# node.net
KiCad netlist of a schematic drawn in EAGLE
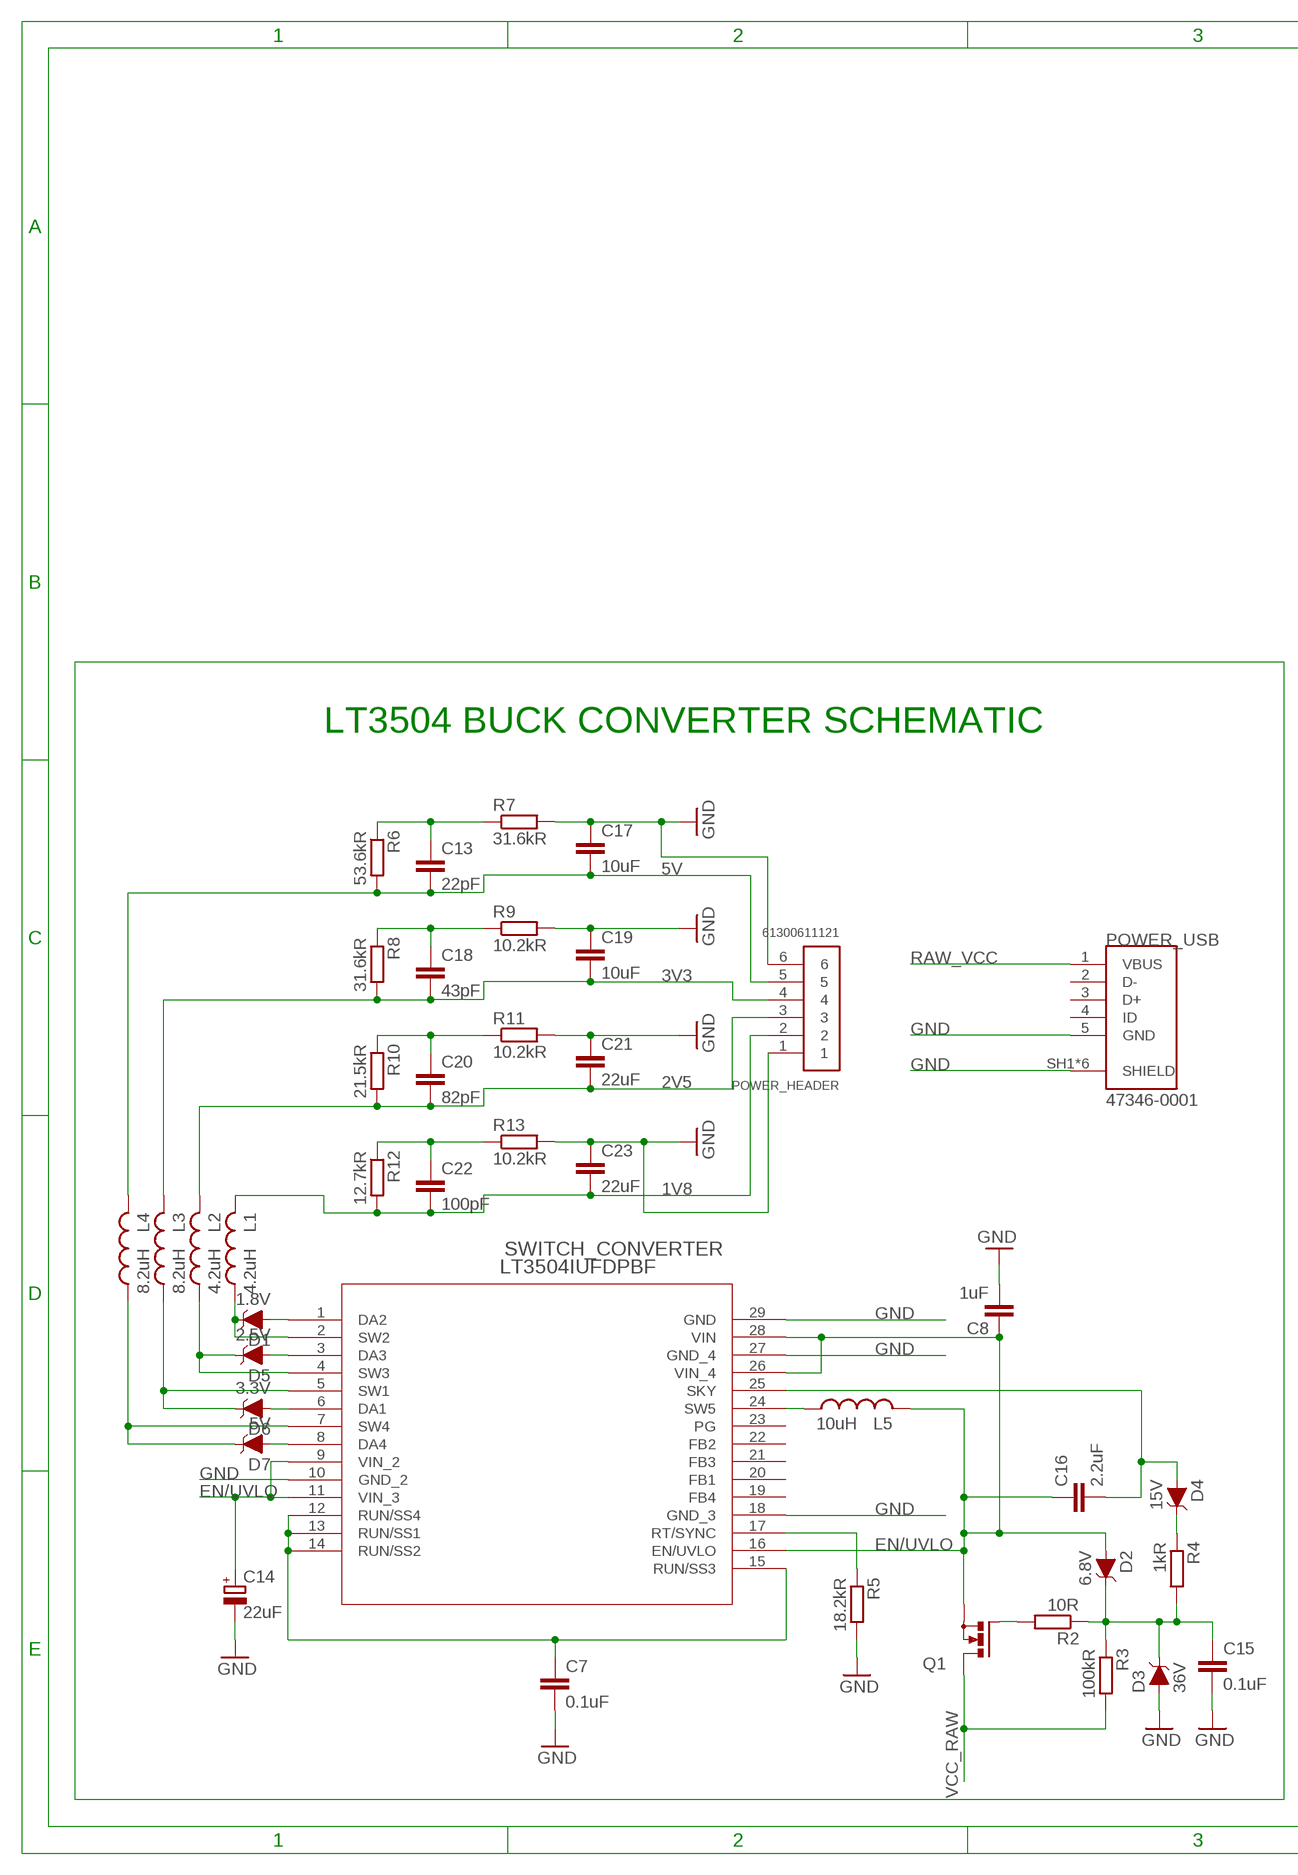
[diagram p0: schematic, sheet 1, part 1 of 2]
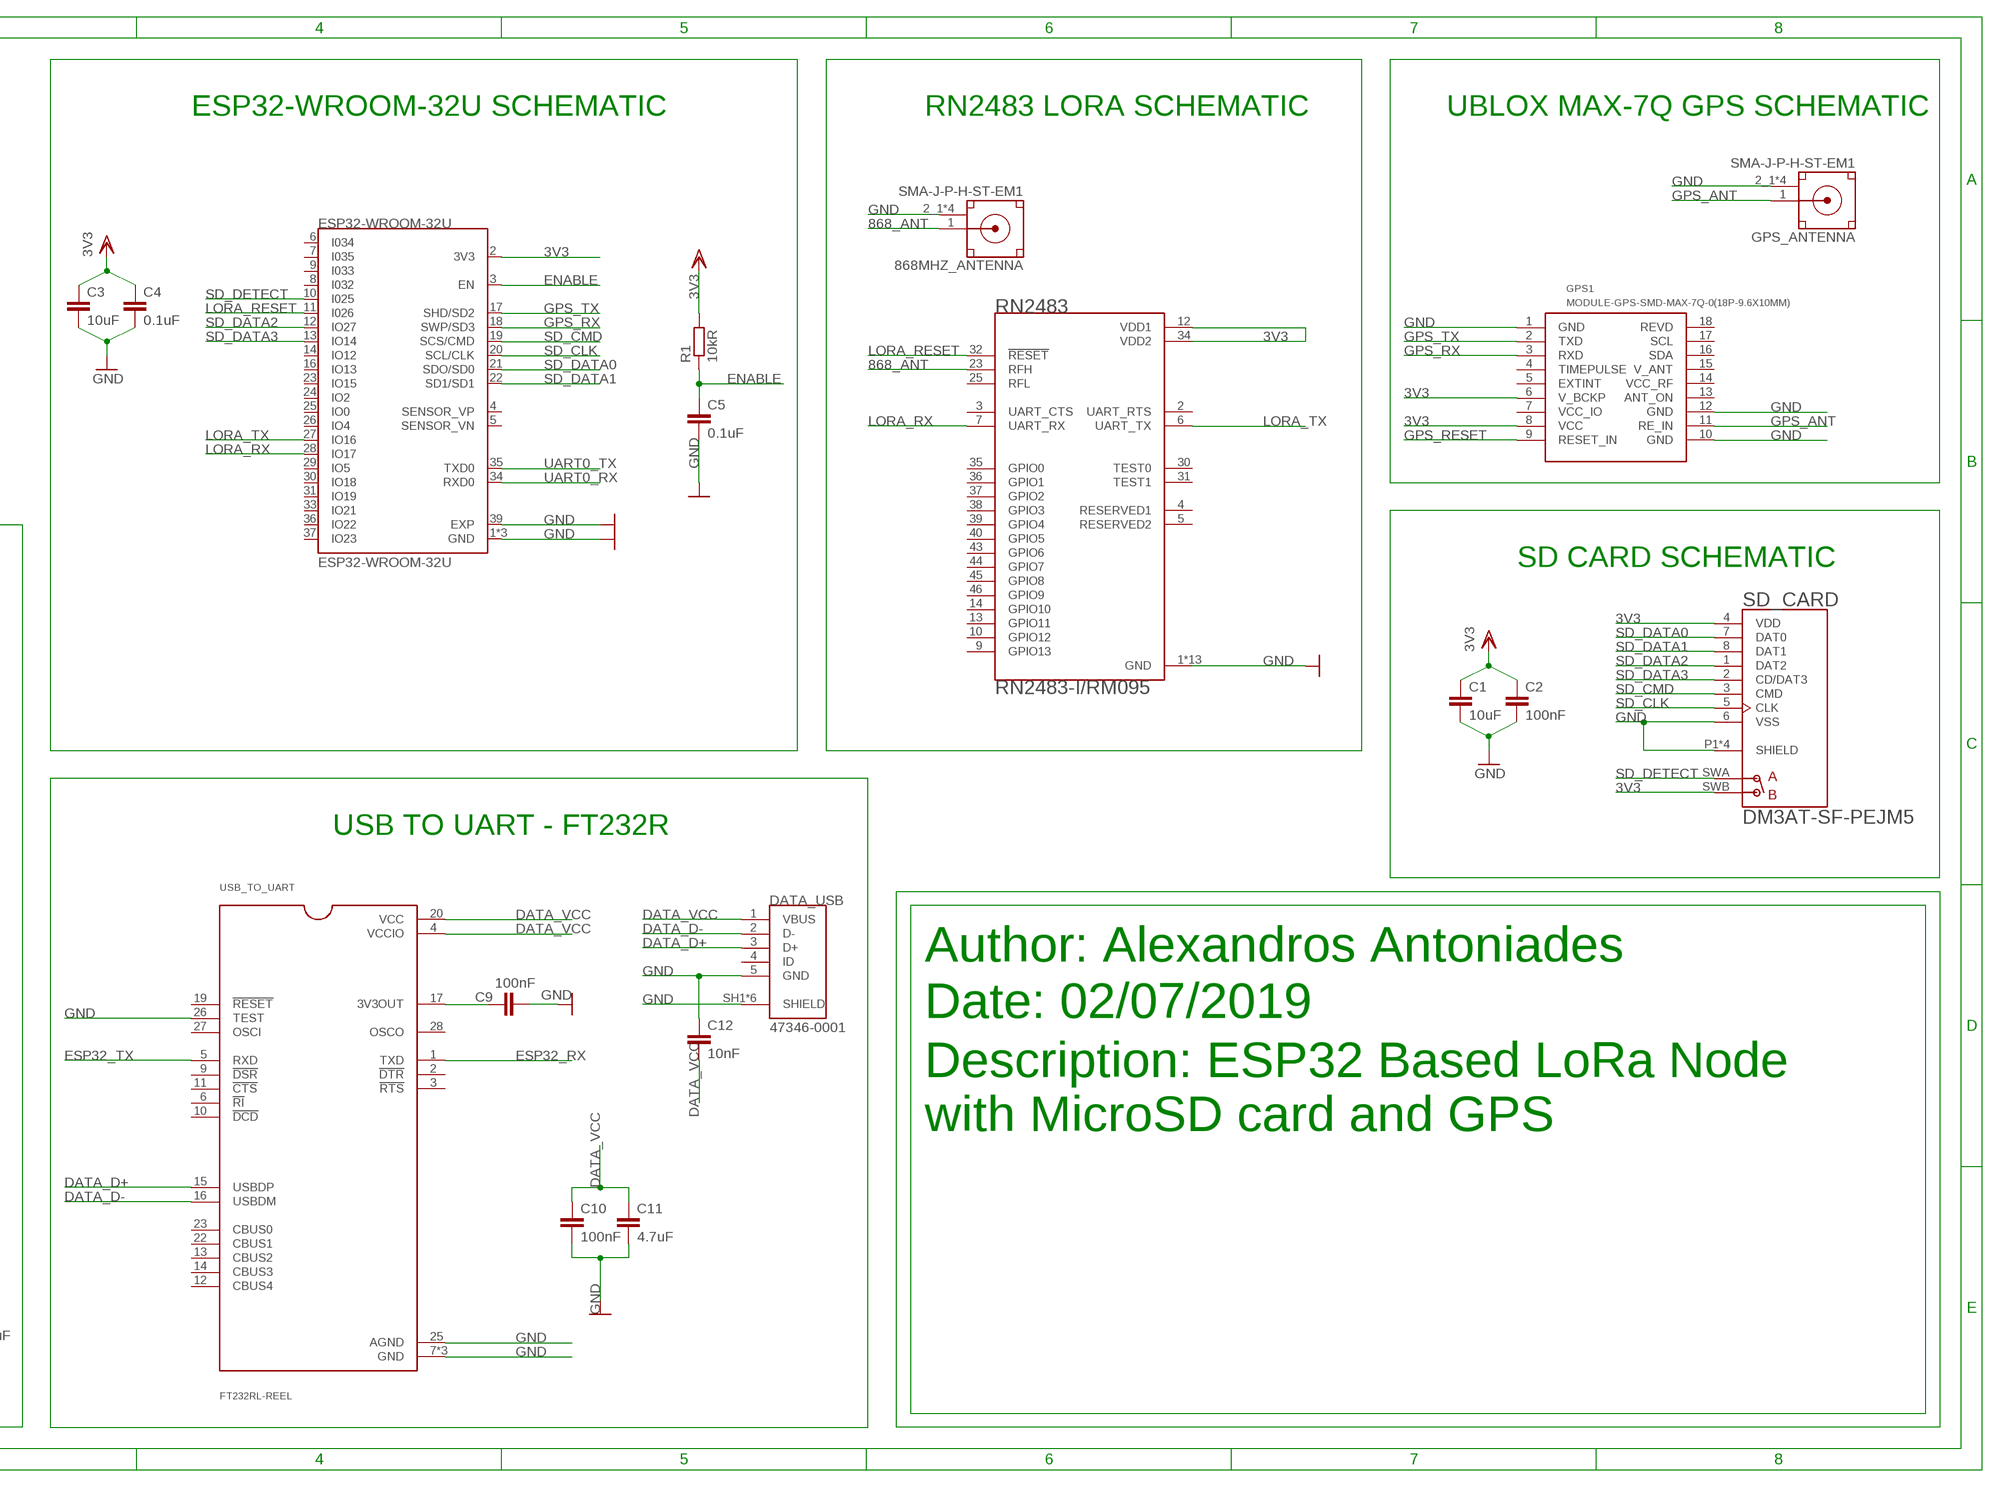
[diagram p1: schematic, sheet 1, part 2 of 2]

(export (version "E")
  (design (tool "Eeschema 10.0.6"))
  (components
    (comp (ref "868MHZ_ANTENNA")
      (value "SMA-J-P-H-ST-EM1")
      (footprint "eagle-import:SMA-J-P-H-ST-EM1")
      (fields (field (name "MF") "Samtec"))
      (libsource (lib "eagle-import") (part "SMA-J-P-H-ST-EM1"))
    )
    (comp (ref "C1")
      (value "10uF")
      (footprint "eagle-import:C0603")
      (libsource (lib "eagle-import") (part "C-EUC0603"))
    )
    (comp (ref "C2")
      (value "100nF")
      (footprint "eagle-import:C0603")
      (libsource (lib "eagle-import") (part "C-EUC0603"))
    )
    (comp (ref "C3")
      (value "10uF")
      (footprint "eagle-import:C0603")
      (libsource (lib "eagle-import") (part "C-EUC0603"))
    )
    (comp (ref "C4")
      (value "0.1uF")
      (footprint "eagle-import:C0603")
      (libsource (lib "eagle-import") (part "C-EUC0603"))
    )
    (comp (ref "C5")
      (value "0.1uF")
      (footprint "eagle-import:C0603")
      (libsource (lib "eagle-import") (part "C-EUC0603"))
    )
    (comp (ref "C7")
      (value "0.1uF")
      (footprint "eagle-import:C0603")
      (libsource (lib "eagle-import") (part "C-EUC0603"))
    )
    (comp (ref "C8")
      (value "1uF")
      (footprint "eagle-import:C0603")
      (libsource (lib "eagle-import") (part "C-EUC0603"))
    )
    (comp (ref "C9")
      (value "100nF")
      (footprint "eagle-import:C0603")
      (libsource (lib "eagle-import") (part "C-EUC0603"))
    )
    (comp (ref "C10")
      (value "100nF")
      (footprint "eagle-import:C0603")
      (libsource (lib "eagle-import") (part "C-EUC0603"))
    )
    (comp (ref "C11")
      (value "4.7uF")
      (footprint "eagle-import:C0603")
      (libsource (lib "eagle-import") (part "C-EUC0603"))
    )
    (comp (ref "C12")
      (value "10nF")
      (footprint "eagle-import:C0603")
      (libsource (lib "eagle-import") (part "C-EUC0603"))
    )
    (comp (ref "C13")
      (value "22pF")
      (footprint "eagle-import:C0603")
      (libsource (lib "eagle-import") (part "C-EUC0603"))
    )
    (comp (ref "C14")
      (value "22uF")
      (footprint "eagle-import:PANASONIC_C")
      (libsource (lib "eagle-import") (part "CPOL-EUC"))
    )
    (comp (ref "C15")
      (value "0.1uF")
      (footprint "eagle-import:C0603")
      (libsource (lib "eagle-import") (part "C-EUC0603"))
    )
    (comp (ref "C16")
      (value "2.2uF")
      (footprint "eagle-import:C0603")
      (libsource (lib "eagle-import") (part "C-EUC0603"))
    )
    (comp (ref "C17")
      (value "10uF")
      (footprint "eagle-import:C0603")
      (libsource (lib "eagle-import") (part "C-EUC0603"))
    )
    (comp (ref "C18")
      (value "43pF")
      (footprint "eagle-import:C0603")
      (libsource (lib "eagle-import") (part "C-EUC0603"))
    )
    (comp (ref "C19")
      (value "10uF")
      (footprint "eagle-import:C0603")
      (libsource (lib "eagle-import") (part "C-EUC0603"))
    )
    (comp (ref "C20")
      (value "82pF")
      (footprint "eagle-import:C0603")
      (libsource (lib "eagle-import") (part "C-EUC0603"))
    )
    (comp (ref "C21")
      (value "22uF")
      (footprint "eagle-import:C0603")
      (libsource (lib "eagle-import") (part "C-EUC0603"))
    )
    (comp (ref "C22")
      (value "100pF")
      (footprint "eagle-import:C0603")
      (libsource (lib "eagle-import") (part "C-EUC0603"))
    )
    (comp (ref "C23")
      (value "22uF")
      (footprint "eagle-import:C0603")
      (libsource (lib "eagle-import") (part "C-EUC0603"))
    )
    (comp (ref "D1")
      (value "1.8V")
      (footprint "eagle-import:PANASONIC_SMINI2-F5-B")
      (libsource (lib "eagle-import") (part "DIODE-ZENER-DZ2J150M0L"))
    )
    (comp (ref "D2")
      (value "6.8V")
      (footprint "eagle-import:PANASONIC_SMINI2-F5-B")
      (libsource (lib "eagle-import") (part "DIODE-ZENER-DZ2J150M0L"))
    )
    (comp (ref "D3")
      (value "36V")
      (footprint "eagle-import:PANASONIC_SMINI2-F5-B")
      (libsource (lib "eagle-import") (part "DIODE-ZENER-DZ2J150M0L"))
    )
    (comp (ref "D4")
      (value "15V")
      (footprint "eagle-import:PANASONIC_SMINI2-F5-B")
      (libsource (lib "eagle-import") (part "DIODE-ZENER-DZ2J150M0L"))
    )
    (comp (ref "D5")
      (value "2.5V")
      (footprint "eagle-import:PANASONIC_SMINI2-F5-B")
      (libsource (lib "eagle-import") (part "DIODE-ZENER-DZ2J150M0L"))
    )
    (comp (ref "D6")
      (value "3.3V")
      (footprint "eagle-import:PANASONIC_SMINI2-F5-B")
      (libsource (lib "eagle-import") (part "DIODE-ZENER-DZ2J150M0L"))
    )
    (comp (ref "D7")
      (value "5V")
      (footprint "eagle-import:PANASONIC_SMINI2-F5-B")
      (libsource (lib "eagle-import") (part "DIODE-ZENER-DZ2J150M0L"))
    )
    (comp (ref "DATA_USB")
      (value "47346-0001")
      (footprint "eagle-import:MOLEX_47346-0001")
      (fields (field (name "MF") "Molex"))
      (libsource (lib "eagle-import") (part "47346-0001"))
    )
    (comp (ref "ESP32-WROOM-32U")
      (value "ESP32-WROOM-32U")
      (footprint "eagle-import:XCVR_ESP32-WROOM-32U")
      (fields (field (name "MF") "Espressif Systems"))
      (libsource (lib "eagle-import") (part "ESP32-WROOM-32U"))
    )
    (comp (ref "GPS1")
      (value "MODULE-GPS-SMD-MAX-7Q-0(18P-9.6X10MM)")
      (footprint "eagle-import:GPS18P-SMD-1.1-10X9.6MM")
      (fields (field (name "MF") "u-blox") (field (name "MP") "MAX-7Q-0"))
      (libsource (lib "eagle-import") (part "MODULE-GPS-SMD-MAX-7Q-0(18P-9.6X10MM)"))
    )
    (comp (ref "GPS_ANTENNA")
      (value "SMA-J-P-H-ST-EM1")
      (footprint "eagle-import:SMA-J-P-H-ST-EM1")
      (fields (field (name "MF") "Samtec"))
      (libsource (lib "eagle-import") (part "SMA-J-P-H-ST-EM1"))
    )
    (comp (ref "L1")
      (value "4.2uH")
      (footprint "eagle-import:L4532P")
      (libsource (lib "eagle-import") (part "L-USL4532P"))
    )
    (comp (ref "L2")
      (value "4.2uH")
      (footprint "eagle-import:L4532P")
      (libsource (lib "eagle-import") (part "L-USL4532P"))
    )
    (comp (ref "L3")
      (value "8.2uH")
      (footprint "eagle-import:L4532P")
      (libsource (lib "eagle-import") (part "L-USL4532P"))
    )
    (comp (ref "L4")
      (value "8.2uH")
      (footprint "eagle-import:L4532P")
      (libsource (lib "eagle-import") (part "L-USL4532P"))
    )
    (comp (ref "L5")
      (value "10uH")
      (footprint "eagle-import:L4532P")
      (libsource (lib "eagle-import") (part "L-USL4532P"))
    )
    (comp (ref "POWER_HEADER")
      (value "61300611121")
      (footprint "eagle-import:61300611121")
      (fields
        (field (name "DIGI_KEY_PART_NUMBER") "732-5319-ND")
        (field (name "MANUFACTURER") "Wurth Electronics Inc.")
        (field (name "CREATED_BY") "PCBLayout.com")
      )
      (libsource (lib "eagle-import") (part "61300611121"))
    )
    (comp (ref "POWER_USB")
      (value "47346-0001")
      (footprint "eagle-import:MOLEX_47346-0001")
      (fields (field (name "MF") "Molex"))
      (libsource (lib "eagle-import") (part "47346-0001"))
    )
    (comp (ref "Q1")
      (value "N-MOSFET-SO8S")
      (footprint "eagle-import:SO-08")
      (libsource (lib "eagle-import") (part "N-MOSFET-SO8S"))
    )
    (comp (ref "R1")
      (value "10kR")
      (footprint "eagle-import:R0603")
      (libsource (lib "eagle-import") (part "R-EU_R0603"))
    )
    (comp (ref "R2")
      (value "10R")
      (footprint "eagle-import:R0603")
      (libsource (lib "eagle-import") (part "R-EU_R0603"))
    )
    (comp (ref "R3")
      (value "100kR")
      (footprint "eagle-import:R0603")
      (libsource (lib "eagle-import") (part "R-EU_R0603"))
    )
    (comp (ref "R4")
      (value "1kR")
      (footprint "eagle-import:R0603")
      (libsource (lib "eagle-import") (part "R-EU_R0603"))
    )
    (comp (ref "R5")
      (value "18.2kR")
      (footprint "eagle-import:R0603")
      (libsource (lib "eagle-import") (part "R-EU_R0603"))
    )
    (comp (ref "R6")
      (value "53.6kR")
      (footprint "eagle-import:R0603")
      (libsource (lib "eagle-import") (part "R-EU_R0603"))
    )
    (comp (ref "R7")
      (value "31.6kR")
      (footprint "eagle-import:R0603")
      (libsource (lib "eagle-import") (part "R-EU_R0603"))
    )
    (comp (ref "R8")
      (value "31.6kR")
      (footprint "eagle-import:R0603")
      (libsource (lib "eagle-import") (part "R-EU_R0603"))
    )
    (comp (ref "R9")
      (value "10.2kR")
      (footprint "eagle-import:R0603")
      (libsource (lib "eagle-import") (part "R-EU_R0603"))
    )
    (comp (ref "R10")
      (value "21.5kR")
      (footprint "eagle-import:R0603")
      (libsource (lib "eagle-import") (part "R-EU_R0603"))
    )
    (comp (ref "R11")
      (value "10.2kR")
      (footprint "eagle-import:R0603")
      (libsource (lib "eagle-import") (part "R-EU_R0603"))
    )
    (comp (ref "R12")
      (value "12.7kR")
      (footprint "eagle-import:R0603")
      (libsource (lib "eagle-import") (part "R-EU_R0603"))
    )
    (comp (ref "R13")
      (value "10.2kR")
      (footprint "eagle-import:R0603")
      (libsource (lib "eagle-import") (part "R-EU_R0603"))
    )
    (comp (ref "RN2483")
      (value "RN2483-I/RM095")
      (footprint "eagle-import:MICROCHIP_RN2483-I_RM095")
      (fields (field (name "MF") "Microchip"))
      (libsource (lib "eagle-import") (part "RN2483-I/RM095"))
    )
    (comp (ref "SD_CARD")
      (value "DM3AT-SF-PEJM5")
      (footprint "eagle-import:HRS_DM3AT-SF-PEJM5")
      (fields (field (name "MF") "Hirose"))
      (libsource (lib "eagle-import") (part "DM3AT-SF-PEJM5"))
    )
    (comp (ref "SWITCH_CONVERTER")
      (value "LT3504IUFDPBF")
      (footprint "eagle-import:QFN-28_UFD")
      (fields
        (field (name "DIGI-KEY_PART_NUMBER") "LT3504IUFD#PBF-ND")
        (field (name "MF") "Linear Technology")
        (field (name "MP") "LT3504IUFD#PBF")
      )
      (libsource (lib "eagle-import") (part "LT3504IUFDPBF"))
    )
    (comp (ref "USB_TO_UART")
      (value "FT232RL-REEL")
      (footprint "eagle-import:SOP65P780X200-28N")
      (fields (field (name "MF") "FTDI,"))
      (libsource (lib "eagle-import") (part "FT232RL-REEL"))
    )
  )
  (nets
    (net (code "1") (name "/1V8") (class "Default")
      (node (ref "C22") (pin "2") (pinfunction "2_2") (pintype "passive"))
      (node (ref "C23") (pin "2") (pinfunction "2_2") (pintype "passive"))
      (node (ref "L1") (pin "2") (pinfunction "2_2") (pintype "passive"))
      (node (ref "POWER_HEADER") (pin "2") (pinfunction "2_2") (pintype "passive"))
      (node (ref "R12") (pin "2") (pinfunction "2_2") (pintype "passive"))
    )
    (net (code "2") (name "/2V5") (class "Default")
      (node (ref "C20") (pin "2") (pinfunction "2_2") (pintype "passive"))
      (node (ref "C21") (pin "2") (pinfunction "2_2") (pintype "passive"))
      (node (ref "L2") (pin "2") (pinfunction "2_2") (pintype "passive"))
      (node (ref "POWER_HEADER") (pin "3") (pinfunction "3_3") (pintype "passive"))
      (node (ref "R10") (pin "2") (pinfunction "2_2") (pintype "passive"))
    )
    (net (code "3") (name "/5V") (class "Default")
      (node (ref "C13") (pin "2") (pinfunction "2_2") (pintype "passive"))
      (node (ref "C17") (pin "2") (pinfunction "2_2") (pintype "passive"))
      (node (ref "L4") (pin "2") (pinfunction "2_2") (pintype "passive"))
      (node (ref "POWER_HEADER") (pin "5") (pinfunction "5_5") (pintype "passive"))
      (node (ref "R6") (pin "2") (pinfunction "2_2") (pintype "passive"))
    )
    (net (code "4") (name "/868_ANT") (class "Default")
      (node (ref "868MHZ_ANTENNA") (pin "1") (pinfunction "SIGNAL_1") (pintype "passive"))
      (node (ref "RN2483") (pin "23") (pinfunction "RFH_23") (pintype "input"))
    )
    (net (code "5") (name "/DATA_D+") (class "Default")
      (node (ref "DATA_USB") (pin "3") (pinfunction "D+_3") (pintype "bidirectional"))
      (node (ref "USB_TO_UART") (pin "15") (pinfunction "USBDP_15") (pintype "bidirectional"))
    )
    (net (code "6") (name "/DATA_D-") (class "Default")
      (node (ref "DATA_USB") (pin "2") (pinfunction "D-_2") (pintype "bidirectional"))
      (node (ref "USB_TO_UART") (pin "16") (pinfunction "USBDM_16") (pintype "bidirectional"))
    )
    (net (code "7") (name "/DATA_VCC") (class "Default")
      (node (ref "C10") (pin "1") (pinfunction "1_1") (pintype "passive"))
      (node (ref "C11") (pin "1") (pinfunction "1_1") (pintype "passive"))
      (node (ref "C12") (pin "2") (pinfunction "2_2") (pintype "passive"))
      (node (ref "DATA_USB") (pin "1") (pinfunction "VBUS_1") (pintype "power_in"))
      (node (ref "USB_TO_UART") (pin "20") (pinfunction "VCC_20") (pintype "power_in"))
      (node (ref "USB_TO_UART") (pin "4") (pinfunction "VCCIO_4") (pintype "power_in"))
    )
    (net (code "8") (name "/ENABLE") (class "Default")
      (node (ref "C5") (pin "1") (pinfunction "1_1") (pintype "passive"))
      (node (ref "ESP32-WROOM-32U") (pin "3") (pinfunction "EN_3") (pintype "input"))
      (node (ref "R1") (pin "1") (pinfunction "1_1") (pintype "passive"))
    )
    (net (code "9") (name "/EN{slash}UVLO") (class "Default")
      (node (ref "C14") (pin "+") (pinfunction "+_+") (pintype "passive"))
      (node (ref "C16") (pin "1") (pinfunction "1_1") (pintype "passive"))
      (node (ref "C8") (pin "1") (pinfunction "1_1") (pintype "passive"))
      (node (ref "D2") (pin "A") (pinfunction "A_A") (pintype "passive"))
      (node (ref "L5") (pin "2") (pinfunction "2_2") (pintype "passive"))
      (node (ref "Q1") (pin "1") (pinfunction "S_1") (pintype "passive"))
      (node (ref "Q1") (pin "2") (pinfunction "S_2") (pintype "passive"))
      (node (ref "Q1") (pin "3") (pinfunction "S_3") (pintype "passive"))
      (node (ref "SWITCH_CONVERTER") (pin "11") (pinfunction "VIN_3_11") (pintype "input"))
      (node (ref "SWITCH_CONVERTER") (pin "16") (pinfunction "EN/UVLO_16") (pintype "bidirectional"))
      (node (ref "SWITCH_CONVERTER") (pin "26") (pinfunction "VIN_4_26") (pintype "input"))
      (node (ref "SWITCH_CONVERTER") (pin "28") (pinfunction "VIN_28") (pintype "input"))
      (node (ref "SWITCH_CONVERTER") (pin "9") (pinfunction "VIN_2_9") (pintype "input"))
    )
    (net (code "10") (name "/ESP32_RX") (class "Default")
      (node (ref "USB_TO_UART") (pin "1") (pinfunction "TXD_1") (pintype "output"))
    )
    (net (code "11") (name "/ESP32_TX") (class "Default")
      (node (ref "USB_TO_UART") (pin "5") (pinfunction "RXD_5") (pintype "input"))
    )
    (net (code "12") (name "/GPS_ANT") (class "Default")
      (node (ref "GPS1") (pin "11") (pinfunction "RE_IN_11") (pintype "bidirectional"))
      (node (ref "GPS_ANTENNA") (pin "1") (pinfunction "SIGNAL_1") (pintype "passive"))
    )
    (net (code "13") (name "/GPS_RESET") (class "Default")
      (node (ref "GPS1") (pin "9") (pinfunction "RESET_IN_9") (pintype "bidirectional"))
    )
    (net (code "14") (name "/GPS_RX") (class "Default")
      (node (ref "ESP32-WROOM-32U") (pin "18") (pinfunction "SWP/SD3_18") (pintype "bidirectional"))
      (node (ref "GPS1") (pin "3") (pinfunction "RXD_3") (pintype "bidirectional"))
    )
    (net (code "15") (name "/GPS_TX") (class "Default")
      (node (ref "ESP32-WROOM-32U") (pin "17") (pinfunction "SHD/SD2_17") (pintype "bidirectional"))
      (node (ref "GPS1") (pin "2") (pinfunction "TXD_2") (pintype "bidirectional"))
    )
    (net (code "16") (name "/LORA_RESET") (class "Default")
      (node (ref "ESP32-WROOM-32U") (pin "11") (pinfunction "I026_11") (pintype "bidirectional"))
      (node (ref "RN2483") (pin "32") (pinfunction "~{RESET}_32") (pintype "input"))
    )
    (net (code "17") (name "/LORA_RX") (class "Default")
      (node (ref "ESP32-WROOM-32U") (pin "28") (pinfunction "IO17_28") (pintype "bidirectional"))
      (node (ref "RN2483") (pin "7") (pinfunction "UART_RX_7") (pintype "input"))
    )
    (net (code "18") (name "/LORA_TX") (class "Default")
      (node (ref "ESP32-WROOM-32U") (pin "27") (pinfunction "IO16_27") (pintype "bidirectional"))
      (node (ref "RN2483") (pin "6") (pinfunction "UART_TX_6") (pintype "output"))
    )
    (net (code "19") (name "/RAW_VCC") (class "Default")
      (node (ref "POWER_USB") (pin "1") (pinfunction "VBUS_1") (pintype "power_in"))
    )
    (net (code "20") (name "/SD_CLK") (class "Default")
      (node (ref "ESP32-WROOM-32U") (pin "20") (pinfunction "SCL/CLK_20") (pintype "bidirectional"))
      (node (ref "SD_CARD") (pin "5") (pinfunction "CLK_5") (pintype "bidirectional"))
    )
    (net (code "21") (name "/SD_CMD") (class "Default")
      (node (ref "ESP32-WROOM-32U") (pin "19") (pinfunction "SCS/CMD_19") (pintype "bidirectional"))
      (node (ref "SD_CARD") (pin "3") (pinfunction "CMD_3") (pintype "bidirectional"))
    )
    (net (code "22") (name "/SD_DATA0") (class "Default")
      (node (ref "ESP32-WROOM-32U") (pin "21") (pinfunction "SDO/SD0_21") (pintype "bidirectional"))
      (node (ref "SD_CARD") (pin "7") (pinfunction "DAT0_7") (pintype "bidirectional"))
    )
    (net (code "23") (name "/SD_DATA1") (class "Default")
      (node (ref "ESP32-WROOM-32U") (pin "22") (pinfunction "SD1/SD1_22") (pintype "bidirectional"))
      (node (ref "SD_CARD") (pin "8") (pinfunction "DAT1_8") (pintype "bidirectional"))
    )
    (net (code "24") (name "/SD_DATA2") (class "Default")
      (node (ref "ESP32-WROOM-32U") (pin "12") (pinfunction "IO27_12") (pintype "bidirectional"))
      (node (ref "SD_CARD") (pin "1") (pinfunction "DAT2_1") (pintype "bidirectional"))
    )
    (net (code "25") (name "/SD_DATA3") (class "Default")
      (node (ref "ESP32-WROOM-32U") (pin "13") (pinfunction "IO14_13") (pintype "bidirectional"))
      (node (ref "SD_CARD") (pin "2") (pinfunction "CD/DAT3_2") (pintype "bidirectional"))
    )
    (net (code "26") (name "/SD_DETECT") (class "Default")
      (node (ref "ESP32-WROOM-32U") (pin "10") (pinfunction "I025_10") (pintype "bidirectional"))
      (node (ref "SD_CARD") (pin "SWA") (pinfunction "A_SWA") (pintype "bidirectional"))
    )
    (net (code "27") (name "/UART0_RX") (class "Default")
      (node (ref "ESP32-WROOM-32U") (pin "34") (pinfunction "RXD0_34") (pintype "bidirectional"))
    )
    (net (code "28") (name "/UART0_TX") (class "Default")
      (node (ref "ESP32-WROOM-32U") (pin "35") (pinfunction "TXD0_35") (pintype "bidirectional"))
    )
    (net (code "29") (name "/VCC_RAW") (class "Default")
      (node (ref "Q1") (pin "5") (pinfunction "D_5") (pintype "passive"))
      (node (ref "Q1") (pin "6") (pinfunction "D_6") (pintype "passive"))
      (node (ref "Q1") (pin "7") (pinfunction "D_7") (pintype "passive"))
      (node (ref "Q1") (pin "8") (pinfunction "D_8") (pintype "passive"))
      (node (ref "R3") (pin "2") (pinfunction "2_2") (pintype "passive"))
    )
    (net (code "30") (name "GND") (class "Default")
      (node (ref "868MHZ_ANTENNA") (pin "2_1") (pinfunction "GND_2_1") (pintype "power_in"))
      (node (ref "868MHZ_ANTENNA") (pin "2_2") (pinfunction "GND_2_2") (pintype "power_in"))
      (node (ref "868MHZ_ANTENNA") (pin "3_1") (pinfunction "GND_3_1") (pintype "power_in"))
      (node (ref "868MHZ_ANTENNA") (pin "3_2") (pinfunction "GND_3_2") (pintype "power_in"))
      (node (ref "C1") (pin "2") (pinfunction "2_2") (pintype "passive"))
      (node (ref "C10") (pin "2") (pinfunction "2_2") (pintype "passive"))
      (node (ref "C11") (pin "2") (pinfunction "2_2") (pintype "passive"))
      (node (ref "C12") (pin "1") (pinfunction "1_1") (pintype "passive"))
      (node (ref "C14") (pin "-") (pinfunction "-_-") (pintype "passive"))
      (node (ref "C15") (pin "2") (pinfunction "2_2") (pintype "passive"))
      (node (ref "C17") (pin "1") (pinfunction "1_1") (pintype "passive"))
      (node (ref "C19") (pin "1") (pinfunction "1_1") (pintype "passive"))
      (node (ref "C2") (pin "2") (pinfunction "2_2") (pintype "passive"))
      (node (ref "C21") (pin "1") (pinfunction "1_1") (pintype "passive"))
      (node (ref "C23") (pin "1") (pinfunction "1_1") (pintype "passive"))
      (node (ref "C3") (pin "2") (pinfunction "2_2") (pintype "passive"))
      (node (ref "C4") (pin "2") (pinfunction "2_2") (pintype "passive"))
      (node (ref "C5") (pin "2") (pinfunction "2_2") (pintype "passive"))
      (node (ref "C7") (pin "2") (pinfunction "2_2") (pintype "passive"))
      (node (ref "C8") (pin "2") (pinfunction "2_2") (pintype "passive"))
      (node (ref "C9") (pin "2") (pinfunction "2_2") (pintype "passive"))
      (node (ref "D3") (pin "A") (pinfunction "A_A") (pintype "passive"))
      (node (ref "DATA_USB") (pin "5") (pinfunction "GND_5") (pintype "power_in"))
      (node (ref "DATA_USB") (pin "SH1") (pinfunction "SHIELD_SH1") (pintype "passive"))
      (node (ref "DATA_USB") (pin "SH2") (pinfunction "SHIELD_SH2") (pintype "passive"))
      (node (ref "DATA_USB") (pin "SH3") (pinfunction "SHIELD_SH3") (pintype "passive"))
      (node (ref "DATA_USB") (pin "SH4") (pinfunction "SHIELD_SH4") (pintype "passive"))
      (node (ref "DATA_USB") (pin "SH5") (pinfunction "SHIELD_SH5") (pintype "passive"))
      (node (ref "DATA_USB") (pin "SH6") (pinfunction "SHIELD_SH6") (pintype "passive"))
      (node (ref "ESP32-WROOM-32U") (pin "1") (pinfunction "GND_1") (pintype "power_in"))
      (node (ref "ESP32-WROOM-32U") (pin "15") (pinfunction "GND_15") (pintype "power_in"))
      (node (ref "ESP32-WROOM-32U") (pin "38") (pinfunction "GND_38") (pintype "power_in"))
      (node (ref "ESP32-WROOM-32U") (pin "39") (pinfunction "EXP_39") (pintype "power_in"))
      (node (ref "GPS1") (pin "1") (pinfunction "GND_1") (pintype "bidirectional"))
      (node (ref "GPS1") (pin "10") (pinfunction "GND_10") (pintype "bidirectional"))
      (node (ref "GPS1") (pin "12") (pinfunction "GND_12") (pintype "bidirectional"))
      (node (ref "GPS_ANTENNA") (pin "2_1") (pinfunction "GND_2_1") (pintype "power_in"))
      (node (ref "GPS_ANTENNA") (pin "2_2") (pinfunction "GND_2_2") (pintype "power_in"))
      (node (ref "GPS_ANTENNA") (pin "3_1") (pinfunction "GND_3_1") (pintype "power_in"))
      (node (ref "GPS_ANTENNA") (pin "3_2") (pinfunction "GND_3_2") (pintype "power_in"))
      (node (ref "POWER_HEADER") (pin "1") (pinfunction "1_1") (pintype "passive"))
      (node (ref "POWER_HEADER") (pin "6") (pinfunction "6_6") (pintype "passive"))
      (node (ref "POWER_USB") (pin "5") (pinfunction "GND_5") (pintype "power_in"))
      (node (ref "POWER_USB") (pin "SH1") (pinfunction "SHIELD_SH1") (pintype "passive"))
      (node (ref "POWER_USB") (pin "SH2") (pinfunction "SHIELD_SH2") (pintype "passive"))
      (node (ref "POWER_USB") (pin "SH3") (pinfunction "SHIELD_SH3") (pintype "passive"))
      (node (ref "POWER_USB") (pin "SH4") (pinfunction "SHIELD_SH4") (pintype "passive"))
      (node (ref "POWER_USB") (pin "SH5") (pinfunction "SHIELD_SH5") (pintype "passive"))
      (node (ref "POWER_USB") (pin "SH6") (pinfunction "SHIELD_SH6") (pintype "passive"))
      (node (ref "R11") (pin "2") (pinfunction "2_2") (pintype "passive"))
      (node (ref "R13") (pin "2") (pinfunction "2_2") (pintype "passive"))
      (node (ref "R5") (pin "2") (pinfunction "2_2") (pintype "passive"))
      (node (ref "R7") (pin "2") (pinfunction "2_2") (pintype "passive"))
      (node (ref "R9") (pin "2") (pinfunction "2_2") (pintype "passive"))
      (node (ref "RN2483") (pin "1") (pinfunction "GND_1") (pintype "passive"))
      (node (ref "RN2483") (pin "11") (pinfunction "GND_11") (pintype "passive"))
      (node (ref "RN2483") (pin "20") (pinfunction "GND_20") (pintype "passive"))
      (node (ref "RN2483") (pin "21") (pinfunction "GND_21") (pintype "passive"))
      (node (ref "RN2483") (pin "22") (pinfunction "GND_22") (pintype "passive"))
      (node (ref "RN2483") (pin "24") (pinfunction "GND_24") (pintype "passive"))
      (node (ref "RN2483") (pin "26") (pinfunction "GND_26") (pintype "passive"))
      (node (ref "RN2483") (pin "27") (pinfunction "GND_27") (pintype "passive"))
      (node (ref "RN2483") (pin "28") (pinfunction "GND_28") (pintype "passive"))
      (node (ref "RN2483") (pin "33") (pinfunction "GND_33") (pintype "passive"))
      (node (ref "RN2483") (pin "41") (pinfunction "GND_41") (pintype "passive"))
      (node (ref "RN2483") (pin "47") (pinfunction "GND_47") (pintype "passive"))
      (node (ref "RN2483") (pin "8") (pinfunction "GND_8") (pintype "passive"))
      (node (ref "SD_CARD") (pin "6") (pinfunction "VSS_6") (pintype "power_in"))
      (node (ref "SD_CARD") (pin "P1") (pinfunction "SHIELD_P1") (pintype "passive"))
      (node (ref "SD_CARD") (pin "P2") (pinfunction "SHIELD_P2") (pintype "passive"))
      (node (ref "SD_CARD") (pin "P3") (pinfunction "SHIELD_P3") (pintype "passive"))
      (node (ref "SD_CARD") (pin "P4") (pinfunction "SHIELD_P4") (pintype "passive"))
      (node (ref "SWITCH_CONVERTER") (pin "10") (pinfunction "GND_2_10") (pintype "power_in"))
      (node (ref "SWITCH_CONVERTER") (pin "18") (pinfunction "GND_3_18") (pintype "power_in"))
      (node (ref "SWITCH_CONVERTER") (pin "27") (pinfunction "GND_4_27") (pintype "power_in"))
      (node (ref "SWITCH_CONVERTER") (pin "29") (pinfunction "GND_29") (pintype "power_in"))
      (node (ref "USB_TO_UART") (pin "18") (pinfunction "GND_18") (pintype "passive"))
      (node (ref "USB_TO_UART") (pin "21") (pinfunction "GND_21") (pintype "passive"))
      (node (ref "USB_TO_UART") (pin "25") (pinfunction "AGND_25") (pintype "passive"))
      (node (ref "USB_TO_UART") (pin "26") (pinfunction "TEST_26") (pintype "input"))
      (node (ref "USB_TO_UART") (pin "7") (pinfunction "GND_7") (pintype "passive"))
    )
    (net (code "31") (name "Net-(C13-Pad1)") (class "Default")
      (node (ref "C13") (pin "1") (pinfunction "1_1") (pintype "passive"))
      (node (ref "R6") (pin "1") (pinfunction "1_1") (pintype "passive"))
      (node (ref "R7") (pin "1") (pinfunction "1_1") (pintype "passive"))
    )
    (net (code "32") (name "Net-(C15-Pad1)") (class "Default")
      (node (ref "C15") (pin "1") (pinfunction "1_1") (pintype "passive"))
      (node (ref "D2") (pin "C") (pinfunction "C_C") (pintype "passive"))
      (node (ref "D3") (pin "C") (pinfunction "C_C") (pintype "passive"))
      (node (ref "R2") (pin "1") (pinfunction "1_1") (pintype "passive"))
      (node (ref "R3") (pin "1") (pinfunction "1_1") (pintype "passive"))
      (node (ref "R4") (pin "2") (pinfunction "2_2") (pintype "passive"))
    )
    (net (code "33") (name "Net-(C18-Pad1)") (class "Default")
      (node (ref "C18") (pin "1") (pinfunction "1_1") (pintype "passive"))
      (node (ref "R8") (pin "1") (pinfunction "1_1") (pintype "passive"))
      (node (ref "R9") (pin "1") (pinfunction "1_1") (pintype "passive"))
    )
    (net (code "34") (name "Net-(C20-Pad1)") (class "Default")
      (node (ref "C20") (pin "1") (pinfunction "1_1") (pintype "passive"))
      (node (ref "R10") (pin "1") (pinfunction "1_1") (pintype "passive"))
      (node (ref "R11") (pin "1") (pinfunction "1_1") (pintype "passive"))
    )
    (net (code "35") (name "Net-(C22-Pad1)") (class "Default")
      (node (ref "C22") (pin "1") (pinfunction "1_1") (pintype "passive"))
      (node (ref "R12") (pin "1") (pinfunction "1_1") (pintype "passive"))
      (node (ref "R13") (pin "1") (pinfunction "1_1") (pintype "passive"))
    )
    (net (code "36") (name "Net-(D4-PadC)") (class "Default")
      (node (ref "D4") (pin "C") (pinfunction "C_C") (pintype "passive"))
      (node (ref "R4") (pin "1") (pinfunction "1_1") (pintype "passive"))
    )
    (net (code "37") (name "Net-(Q1-G)") (class "Default")
      (node (ref "Q1") (pin "4") (pinfunction "G_4") (pintype "passive"))
      (node (ref "R2") (pin "2") (pinfunction "2_2") (pintype "passive"))
    )
    (net (code "38") (name "Net-(SWITCH_CONVERTER-DA1)") (class "Default")
      (node (ref "D6") (pin "A") (pinfunction "A_A") (pintype "passive"))
      (node (ref "SWITCH_CONVERTER") (pin "6") (pinfunction "DA1_6") (pintype "passive"))
    )
    (net (code "39") (name "Net-(SWITCH_CONVERTER-DA2)") (class "Default")
      (node (ref "D1") (pin "A") (pinfunction "A_A") (pintype "passive"))
      (node (ref "SWITCH_CONVERTER") (pin "1") (pinfunction "DA2_1") (pintype "passive"))
    )
    (net (code "40") (name "Net-(SWITCH_CONVERTER-DA3)") (class "Default")
      (node (ref "D5") (pin "A") (pinfunction "A_A") (pintype "passive"))
      (node (ref "SWITCH_CONVERTER") (pin "3") (pinfunction "DA3_3") (pintype "passive"))
    )
    (net (code "41") (name "Net-(SWITCH_CONVERTER-DA4)") (class "Default")
      (node (ref "D7") (pin "A") (pinfunction "A_A") (pintype "passive"))
      (node (ref "SWITCH_CONVERTER") (pin "8") (pinfunction "DA4_8") (pintype "passive"))
    )
    (net (code "42") (name "Net-(SWITCH_CONVERTER-RT{slash}SYNC)") (class "Default")
      (node (ref "R5") (pin "1") (pinfunction "1_1") (pintype "passive"))
      (node (ref "SWITCH_CONVERTER") (pin "17") (pinfunction "RT/SYNC_17") (pintype "bidirectional"))
    )
    (net (code "43") (name "Net-(SWITCH_CONVERTER-RUN{slash}SS1)") (class "Default")
      (node (ref "C7") (pin "1") (pinfunction "1_1") (pintype "passive"))
      (node (ref "SWITCH_CONVERTER") (pin "12") (pinfunction "RUN/SS4_12") (pintype "output"))
      (node (ref "SWITCH_CONVERTER") (pin "13") (pinfunction "RUN/SS1_13") (pintype "output"))
      (node (ref "SWITCH_CONVERTER") (pin "14") (pinfunction "RUN/SS2_14") (pintype "output"))
      (node (ref "SWITCH_CONVERTER") (pin "15") (pinfunction "RUN/SS3_15") (pintype "output"))
    )
    (net (code "44") (name "Net-(SWITCH_CONVERTER-SKY)") (class "Default")
      (node (ref "C16") (pin "2") (pinfunction "2_2") (pintype "passive"))
      (node (ref "D4") (pin "A") (pinfunction "A_A") (pintype "passive"))
      (node (ref "SWITCH_CONVERTER") (pin "25") (pinfunction "SKY_25") (pintype "output"))
    )
    (net (code "45") (name "Net-(SWITCH_CONVERTER-SW1)") (class "Default")
      (node (ref "D6") (pin "C") (pinfunction "C_C") (pintype "passive"))
      (node (ref "L3") (pin "1") (pinfunction "1_1") (pintype "passive"))
      (node (ref "SWITCH_CONVERTER") (pin "5") (pinfunction "SW1_5") (pintype "output"))
    )
    (net (code "46") (name "Net-(SWITCH_CONVERTER-SW2)") (class "Default")
      (node (ref "D1") (pin "C") (pinfunction "C_C") (pintype "passive"))
      (node (ref "L1") (pin "1") (pinfunction "1_1") (pintype "passive"))
      (node (ref "SWITCH_CONVERTER") (pin "2") (pinfunction "SW2_2") (pintype "output"))
    )
    (net (code "47") (name "Net-(SWITCH_CONVERTER-SW3)") (class "Default")
      (node (ref "D5") (pin "C") (pinfunction "C_C") (pintype "passive"))
      (node (ref "L2") (pin "1") (pinfunction "1_1") (pintype "passive"))
      (node (ref "SWITCH_CONVERTER") (pin "4") (pinfunction "SW3_4") (pintype "output"))
    )
    (net (code "48") (name "Net-(SWITCH_CONVERTER-SW4)") (class "Default")
      (node (ref "D7") (pin "C") (pinfunction "C_C") (pintype "passive"))
      (node (ref "L4") (pin "1") (pinfunction "1_1") (pintype "passive"))
      (node (ref "SWITCH_CONVERTER") (pin "7") (pinfunction "SW4_7") (pintype "output"))
    )
    (net (code "49") (name "Net-(SWITCH_CONVERTER-SW5)") (class "Default")
      (node (ref "L5") (pin "1") (pinfunction "1_1") (pintype "passive"))
      (node (ref "SWITCH_CONVERTER") (pin "24") (pinfunction "SW5_24") (pintype "passive"))
    )
    (net (code "50") (name "Net-(USB_TO_UART-3V3OUT)") (class "Default")
      (node (ref "C9") (pin "1") (pinfunction "1_1") (pintype "passive"))
      (node (ref "USB_TO_UART") (pin "17") (pinfunction "3V3OUT_17") (pintype "output"))
    )
    (net (code "51") (name "VDD") (class "Default")
      (node (ref "C1") (pin "1") (pinfunction "1_1") (pintype "passive"))
      (node (ref "C18") (pin "2") (pinfunction "2_2") (pintype "passive"))
      (node (ref "C19") (pin "2") (pinfunction "2_2") (pintype "passive"))
      (node (ref "C2") (pin "1") (pinfunction "1_1") (pintype "passive"))
      (node (ref "C3") (pin "1") (pinfunction "1_1") (pintype "passive"))
      (node (ref "C4") (pin "1") (pinfunction "1_1") (pintype "passive"))
      (node (ref "ESP32-WROOM-32U") (pin "2") (pinfunction "3V3_2") (pintype "power_in"))
      (node (ref "GPS1") (pin "6") (pinfunction "V_BCKP_6") (pintype "bidirectional"))
      (node (ref "GPS1") (pin "8") (pinfunction "VCC_8") (pintype "bidirectional"))
      (node (ref "L3") (pin "2") (pinfunction "2_2") (pintype "passive"))
      (node (ref "POWER_HEADER") (pin "4") (pinfunction "4_4") (pintype "passive"))
      (node (ref "R1") (pin "2") (pinfunction "2_2") (pintype "passive"))
      (node (ref "R8") (pin "2") (pinfunction "2_2") (pintype "passive"))
      (node (ref "RN2483") (pin "12") (pinfunction "VDD1_12") (pintype "power_in"))
      (node (ref "RN2483") (pin "34") (pinfunction "VDD2_34") (pintype "power_in"))
      (node (ref "SD_CARD") (pin "4") (pinfunction "VDD_4") (pintype "power_in"))
      (node (ref "SD_CARD") (pin "SWB") (pinfunction "B_SWB") (pintype "bidirectional"))
    )
    (net (code "52") (name "unconnected-(DATA_USB-ID-Pad4)") (class "Default")
      (node (ref "DATA_USB") (pin "4") (pinfunction "ID_4") (pintype "passive"))
    )
    (net (code "53") (name "unconnected-(ESP32-WROOM-32U-I032-Pad8)") (class "Default")
      (node (ref "ESP32-WROOM-32U") (pin "8") (pinfunction "I032_8") (pintype "bidirectional"))
    )
    (net (code "54") (name "unconnected-(ESP32-WROOM-32U-I033-Pad9)") (class "Default")
      (node (ref "ESP32-WROOM-32U") (pin "9") (pinfunction "I033_9") (pintype "bidirectional"))
    )
    (net (code "55") (name "unconnected-(ESP32-WROOM-32U-I034-Pad6)") (class "Default")
      (node (ref "ESP32-WROOM-32U") (pin "6") (pinfunction "I034_6") (pintype "input"))
    )
    (net (code "56") (name "unconnected-(ESP32-WROOM-32U-I035-Pad7)") (class "Default")
      (node (ref "ESP32-WROOM-32U") (pin "7") (pinfunction "I035_7") (pintype "input"))
    )
    (net (code "57") (name "unconnected-(ESP32-WROOM-32U-IO0-Pad25)") (class "Default")
      (node (ref "ESP32-WROOM-32U") (pin "25") (pinfunction "IO0_25") (pintype "bidirectional"))
    )
    (net (code "58") (name "unconnected-(ESP32-WROOM-32U-IO2-Pad24)") (class "Default")
      (node (ref "ESP32-WROOM-32U") (pin "24") (pinfunction "IO2_24") (pintype "bidirectional"))
    )
    (net (code "59") (name "unconnected-(ESP32-WROOM-32U-IO4-Pad26)") (class "Default")
      (node (ref "ESP32-WROOM-32U") (pin "26") (pinfunction "IO4_26") (pintype "bidirectional"))
    )
    (net (code "60") (name "unconnected-(ESP32-WROOM-32U-IO5-Pad29)") (class "Default")
      (node (ref "ESP32-WROOM-32U") (pin "29") (pinfunction "IO5_29") (pintype "bidirectional"))
    )
    (net (code "61") (name "unconnected-(ESP32-WROOM-32U-IO12-Pad14)") (class "Default")
      (node (ref "ESP32-WROOM-32U") (pin "14") (pinfunction "IO12_14") (pintype "bidirectional"))
    )
    (net (code "62") (name "unconnected-(ESP32-WROOM-32U-IO13-Pad16)") (class "Default")
      (node (ref "ESP32-WROOM-32U") (pin "16") (pinfunction "IO13_16") (pintype "bidirectional"))
    )
    (net (code "63") (name "unconnected-(ESP32-WROOM-32U-IO15-Pad23)") (class "Default")
      (node (ref "ESP32-WROOM-32U") (pin "23") (pinfunction "IO15_23") (pintype "bidirectional"))
    )
    (net (code "64") (name "unconnected-(ESP32-WROOM-32U-IO18-Pad30)") (class "Default")
      (node (ref "ESP32-WROOM-32U") (pin "30") (pinfunction "IO18_30") (pintype "bidirectional"))
    )
    (net (code "65") (name "unconnected-(ESP32-WROOM-32U-IO19-Pad31)") (class "Default")
      (node (ref "ESP32-WROOM-32U") (pin "31") (pinfunction "IO19_31") (pintype "bidirectional"))
    )
    (net (code "66") (name "unconnected-(ESP32-WROOM-32U-IO21-Pad33)") (class "Default")
      (node (ref "ESP32-WROOM-32U") (pin "33") (pinfunction "IO21_33") (pintype "bidirectional"))
    )
    (net (code "67") (name "unconnected-(ESP32-WROOM-32U-IO22-Pad36)") (class "Default")
      (node (ref "ESP32-WROOM-32U") (pin "36") (pinfunction "IO22_36") (pintype "bidirectional"))
    )
    (net (code "68") (name "unconnected-(ESP32-WROOM-32U-IO23-Pad37)") (class "Default")
      (node (ref "ESP32-WROOM-32U") (pin "37") (pinfunction "IO23_37") (pintype "bidirectional"))
    )
    (net (code "69") (name "unconnected-(ESP32-WROOM-32U-SENSOR_VN-Pad5)") (class "Default")
      (node (ref "ESP32-WROOM-32U") (pin "5") (pinfunction "SENSOR_VN_5") (pintype "input"))
    )
    (net (code "70") (name "unconnected-(ESP32-WROOM-32U-SENSOR_VP-Pad4)") (class "Default")
      (node (ref "ESP32-WROOM-32U") (pin "4") (pinfunction "SENSOR_VP_4") (pintype "input"))
    )
    (net (code "71") (name "unconnected-(GPS1-ANT_ON-Pad13)") (class "Default")
      (node (ref "GPS1") (pin "13") (pinfunction "ANT_ON_13") (pintype "bidirectional"))
    )
    (net (code "72") (name "unconnected-(GPS1-EXTINT-Pad5)") (class "Default")
      (node (ref "GPS1") (pin "5") (pinfunction "EXTINT_5") (pintype "bidirectional"))
    )
    (net (code "73") (name "unconnected-(GPS1-REVD-Pad18)") (class "Default")
      (node (ref "GPS1") (pin "18") (pinfunction "REVD_18") (pintype "bidirectional"))
    )
    (net (code "74") (name "unconnected-(GPS1-SCL-Pad17)") (class "Default")
      (node (ref "GPS1") (pin "17") (pinfunction "SCL_17") (pintype "bidirectional"))
    )
    (net (code "75") (name "unconnected-(GPS1-SDA-Pad16)") (class "Default")
      (node (ref "GPS1") (pin "16") (pinfunction "SDA_16") (pintype "bidirectional"))
    )
    (net (code "76") (name "unconnected-(GPS1-TIMEPULSE-Pad4)") (class "Default")
      (node (ref "GPS1") (pin "4") (pinfunction "TIMEPULSE_4") (pintype "bidirectional"))
    )
    (net (code "77") (name "unconnected-(GPS1-VCC_IO-Pad7)") (class "Default")
      (node (ref "GPS1") (pin "7") (pinfunction "VCC_IO_7") (pintype "bidirectional"))
    )
    (net (code "78") (name "unconnected-(GPS1-VCC_RF-Pad14)") (class "Default")
      (node (ref "GPS1") (pin "14") (pinfunction "VCC_RF_14") (pintype "bidirectional"))
    )
    (net (code "79") (name "unconnected-(GPS1-V_ANT-Pad15)") (class "Default")
      (node (ref "GPS1") (pin "15") (pinfunction "V_ANT_15") (pintype "bidirectional"))
    )
    (net (code "80") (name "unconnected-(POWER_USB-D+-Pad3)") (class "Default")
      (node (ref "POWER_USB") (pin "3") (pinfunction "D+_3") (pintype "bidirectional"))
    )
    (net (code "81") (name "unconnected-(POWER_USB-D--Pad2)") (class "Default")
      (node (ref "POWER_USB") (pin "2") (pinfunction "D-_2") (pintype "bidirectional"))
    )
    (net (code "82") (name "unconnected-(POWER_USB-ID-Pad4)") (class "Default")
      (node (ref "POWER_USB") (pin "4") (pinfunction "ID_4") (pintype "passive"))
    )
    (net (code "83") (name "unconnected-(RN2483-GPIO0-Pad35)") (class "Default")
      (node (ref "RN2483") (pin "35") (pinfunction "GPIO0_35") (pintype "bidirectional"))
    )
    (net (code "84") (name "unconnected-(RN2483-GPIO1-Pad36)") (class "Default")
      (node (ref "RN2483") (pin "36") (pinfunction "GPIO1_36") (pintype "bidirectional"))
    )
    (net (code "85") (name "unconnected-(RN2483-GPIO2-Pad37)") (class "Default")
      (node (ref "RN2483") (pin "37") (pinfunction "GPIO2_37") (pintype "bidirectional"))
    )
    (net (code "86") (name "unconnected-(RN2483-GPIO3-Pad38)") (class "Default")
      (node (ref "RN2483") (pin "38") (pinfunction "GPIO3_38") (pintype "bidirectional"))
    )
    (net (code "87") (name "unconnected-(RN2483-GPIO4-Pad39)") (class "Default")
      (node (ref "RN2483") (pin "39") (pinfunction "GPIO4_39") (pintype "bidirectional"))
    )
    (net (code "88") (name "unconnected-(RN2483-GPIO5-Pad40)") (class "Default")
      (node (ref "RN2483") (pin "40") (pinfunction "GPIO5_40") (pintype "bidirectional"))
    )
    (net (code "89") (name "unconnected-(RN2483-GPIO6-Pad43)") (class "Default")
      (node (ref "RN2483") (pin "43") (pinfunction "GPIO6_43") (pintype "bidirectional"))
    )
    (net (code "90") (name "unconnected-(RN2483-GPIO7-Pad44)") (class "Default")
      (node (ref "RN2483") (pin "44") (pinfunction "GPIO7_44") (pintype "bidirectional"))
    )
    (net (code "91") (name "unconnected-(RN2483-GPIO8-Pad45)") (class "Default")
      (node (ref "RN2483") (pin "45") (pinfunction "GPIO8_45") (pintype "bidirectional"))
    )
    (net (code "92") (name "unconnected-(RN2483-GPIO9-Pad46)") (class "Default")
      (node (ref "RN2483") (pin "46") (pinfunction "GPIO9_46") (pintype "bidirectional"))
    )
    (net (code "93") (name "unconnected-(RN2483-GPIO10-Pad14)") (class "Default")
      (node (ref "RN2483") (pin "14") (pinfunction "GPIO10_14") (pintype "bidirectional"))
    )
    (net (code "94") (name "unconnected-(RN2483-GPIO11-Pad13)") (class "Default")
      (node (ref "RN2483") (pin "13") (pinfunction "GPIO11_13") (pintype "bidirectional"))
    )
    (net (code "95") (name "unconnected-(RN2483-GPIO12-Pad10)") (class "Default")
      (node (ref "RN2483") (pin "10") (pinfunction "GPIO12_10") (pintype "bidirectional"))
    )
    (net (code "96") (name "unconnected-(RN2483-GPIO13-Pad9)") (class "Default")
      (node (ref "RN2483") (pin "9") (pinfunction "GPIO13_9") (pintype "bidirectional"))
    )
    (net (code "97") (name "unconnected-(RN2483-RESERVED1-Pad4)") (class "Default")
      (node (ref "RN2483") (pin "4") (pinfunction "RESERVED1_4") (pintype "passive"))
    )
    (net (code "98") (name "unconnected-(RN2483-RESERVED2-Pad5)") (class "Default")
      (node (ref "RN2483") (pin "5") (pinfunction "RESERVED2_5") (pintype "passive"))
    )
    (net (code "99") (name "unconnected-(RN2483-RFL-Pad25)") (class "Default")
      (node (ref "RN2483") (pin "25") (pinfunction "RFL_25") (pintype "input"))
    )
    (net (code "100") (name "unconnected-(RN2483-TEST0-Pad30)") (class "Default")
      (node (ref "RN2483") (pin "30") (pinfunction "TEST0_30") (pintype "passive"))
    )
    (net (code "101") (name "unconnected-(RN2483-TEST1-Pad31)") (class "Default")
      (node (ref "RN2483") (pin "31") (pinfunction "TEST1_31") (pintype "passive"))
    )
    (net (code "102") (name "unconnected-(RN2483-UART_CTS-Pad3)") (class "Default")
      (node (ref "RN2483") (pin "3") (pinfunction "UART_CTS_3") (pintype "input"))
    )
    (net (code "103") (name "unconnected-(RN2483-UART_RTS-Pad2)") (class "Default")
      (node (ref "RN2483") (pin "2") (pinfunction "UART_RTS_2") (pintype "output"))
    )
    (net (code "104") (name "unconnected-(SWITCH_CONVERTER-FB1-Pad20)") (class "Default")
      (node (ref "SWITCH_CONVERTER") (pin "20") (pinfunction "FB1_20") (pintype "output"))
    )
    (net (code "105") (name "unconnected-(SWITCH_CONVERTER-FB2-Pad22)") (class "Default")
      (node (ref "SWITCH_CONVERTER") (pin "22") (pinfunction "FB2_22") (pintype "output"))
    )
    (net (code "106") (name "unconnected-(SWITCH_CONVERTER-FB3-Pad21)") (class "Default")
      (node (ref "SWITCH_CONVERTER") (pin "21") (pinfunction "FB3_21") (pintype "output"))
    )
    (net (code "107") (name "unconnected-(SWITCH_CONVERTER-FB4-Pad19)") (class "Default")
      (node (ref "SWITCH_CONVERTER") (pin "19") (pinfunction "FB4_19") (pintype "output"))
    )
    (net (code "108") (name "unconnected-(SWITCH_CONVERTER-PG-Pad23)") (class "Default")
      (node (ref "SWITCH_CONVERTER") (pin "23") (pinfunction "PG_23") (pintype "output"))
    )
    (net (code "109") (name "unconnected-(USB_TO_UART-CBUS0-Pad23)") (class "Default")
      (node (ref "USB_TO_UART") (pin "23") (pinfunction "CBUS0_23") (pintype "bidirectional"))
    )
    (net (code "110") (name "unconnected-(USB_TO_UART-CBUS1-Pad22)") (class "Default")
      (node (ref "USB_TO_UART") (pin "22") (pinfunction "CBUS1_22") (pintype "bidirectional"))
    )
    (net (code "111") (name "unconnected-(USB_TO_UART-CBUS2-Pad13)") (class "Default")
      (node (ref "USB_TO_UART") (pin "13") (pinfunction "CBUS2_13") (pintype "bidirectional"))
    )
    (net (code "112") (name "unconnected-(USB_TO_UART-CBUS3-Pad14)") (class "Default")
      (node (ref "USB_TO_UART") (pin "14") (pinfunction "CBUS3_14") (pintype "bidirectional"))
    )
    (net (code "113") (name "unconnected-(USB_TO_UART-CBUS4-Pad12)") (class "Default")
      (node (ref "USB_TO_UART") (pin "12") (pinfunction "CBUS4_12") (pintype "bidirectional"))
    )
    (net (code "114") (name "unconnected-(USB_TO_UART-OSCI-Pad27)") (class "Default")
      (node (ref "USB_TO_UART") (pin "27") (pinfunction "OSCI_27") (pintype "input"))
    )
    (net (code "115") (name "unconnected-(USB_TO_UART-OSCO-Pad28)") (class "Default")
      (node (ref "USB_TO_UART") (pin "28") (pinfunction "OSCO_28") (pintype "output"))
    )
    (net (code "116") (name "unconnected-(USB_TO_UART-~{CTS}-Pad11)") (class "Default")
      (node (ref "USB_TO_UART") (pin "11") (pinfunction "~{CTS}_11") (pintype "input"))
    )
    (net (code "117") (name "unconnected-(USB_TO_UART-~{DCD}-Pad10)") (class "Default")
      (node (ref "USB_TO_UART") (pin "10") (pinfunction "~{DCD}_10") (pintype "input"))
    )
    (net (code "118") (name "unconnected-(USB_TO_UART-~{DSR}-Pad9)") (class "Default")
      (node (ref "USB_TO_UART") (pin "9") (pinfunction "~{DSR}_9") (pintype "input"))
    )
    (net (code "119") (name "unconnected-(USB_TO_UART-~{DTR}-Pad2)") (class "Default")
      (node (ref "USB_TO_UART") (pin "2") (pinfunction "~{DTR}_2") (pintype "output"))
    )
    (net (code "120") (name "unconnected-(USB_TO_UART-~{RESET}-Pad19)") (class "Default")
      (node (ref "USB_TO_UART") (pin "19") (pinfunction "~{RESET}_19") (pintype "input"))
    )
    (net (code "121") (name "unconnected-(USB_TO_UART-~{RI}-Pad6)") (class "Default")
      (node (ref "USB_TO_UART") (pin "6") (pinfunction "~{RI}_6") (pintype "input"))
    )
    (net (code "122") (name "unconnected-(USB_TO_UART-~{RTS}-Pad3)") (class "Default")
      (node (ref "USB_TO_UART") (pin "3") (pinfunction "~{RTS}_3") (pintype "output"))
    )
  )
)
